# ball_presence_pht.net
KiCad netlist of a schematic drawn in EAGLE
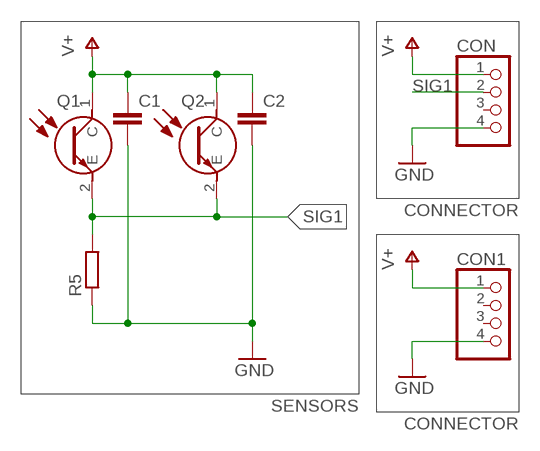
[diagram p0: schematic, sheet 1]

(export (version "E")
  (design (tool "Eeschema 10.0.6"))
  (components
    (comp (ref "C1")
      (value "C-EUC0805")
      (footprint "eagle-import:C0805")
      (libsource (lib "eagle-import") (part "C-EUC0805"))
    )
    (comp (ref "C2")
      (value "C-EUC0805")
      (footprint "eagle-import:C0805")
      (libsource (lib "eagle-import") (part "C-EUC0805"))
    )
    (comp (ref "CON")
      (value "PINHD-1X4")
      (footprint "eagle-import:1X04")
      (libsource (lib "eagle-import") (part "PINHD-1X4"))
    )
    (comp (ref "CON1")
      (value "PINHD-1X4")
      (footprint "eagle-import:1X04")
      (libsource (lib "eagle-import") (part "PINHD-1X4"))
    )
    (comp (ref "Q1")
      (value "VEMT2520X01")
      (footprint "eagle-import:VEMT2520X01")
      (fields
        (field (name "MOUSER_PART_NUMBER") "782-VEMT2520X01")
        (field (name "RS_PART_NUMBER") "7689417P")
      )
      (libsource (lib "eagle-import") (part "VEMT2520X01"))
    )
    (comp (ref "Q2")
      (value "VEMT2520X01")
      (footprint "eagle-import:VEMT2520X01")
      (fields
        (field (name "MOUSER_PART_NUMBER") "782-VEMT2520X01")
        (field (name "RS_PART_NUMBER") "7689417P")
      )
      (libsource (lib "eagle-import") (part "VEMT2520X01"))
    )
    (comp (ref "R5")
      (value "R-EU_R0805")
      (footprint "eagle-import:R0805")
      (libsource (lib "eagle-import") (part "R-EU_R0805"))
    )
  )
  (nets
    (net (code "1") (name "GND") (class "Default")
      (node (ref "C1") (pin "2") (pinfunction "2_2") (pintype "passive"))
      (node (ref "C2") (pin "2") (pinfunction "2_2") (pintype "passive"))
      (node (ref "CON") (pin "4") (pinfunction "4_4") (pintype "passive"))
      (node (ref "CON1") (pin "4") (pinfunction "4_4") (pintype "passive"))
      (node (ref "R5") (pin "1") (pinfunction "1_1") (pintype "passive"))
    )
    (net (code "2") (name "SIG1") (class "Default")
      (node (ref "CON") (pin "2") (pinfunction "2_2") (pintype "passive"))
      (node (ref "Q1") (pin "2") (pinfunction "E_2") (pintype "bidirectional"))
      (node (ref "Q2") (pin "2") (pinfunction "E_2") (pintype "bidirectional"))
      (node (ref "R5") (pin "2") (pinfunction "2_2") (pintype "passive"))
    )
    (net (code "3") (name "V+") (class "Default")
      (node (ref "C1") (pin "1") (pinfunction "1_1") (pintype "passive"))
      (node (ref "C2") (pin "1") (pinfunction "1_1") (pintype "passive"))
      (node (ref "CON") (pin "1") (pinfunction "1_1") (pintype "passive"))
      (node (ref "CON1") (pin "1") (pinfunction "1_1") (pintype "passive"))
      (node (ref "Q1") (pin "1") (pinfunction "C_1") (pintype "bidirectional"))
      (node (ref "Q2") (pin "1") (pinfunction "C_1") (pintype "bidirectional"))
    )
    (net (code "4") (name "unconnected-(CON-Pad3)") (class "Default")
      (node (ref "CON") (pin "3") (pinfunction "3_3") (pintype "passive"))
    )
    (net (code "5") (name "unconnected-(CON1-Pad2)") (class "Default")
      (node (ref "CON1") (pin "2") (pinfunction "2_2") (pintype "passive"))
    )
    (net (code "6") (name "unconnected-(CON1-Pad3)") (class "Default")
      (node (ref "CON1") (pin "3") (pinfunction "3_3") (pintype "passive"))
    )
  )
)
